# ADC.net
KiCad netlist of a schematic drawn in Altium Designer
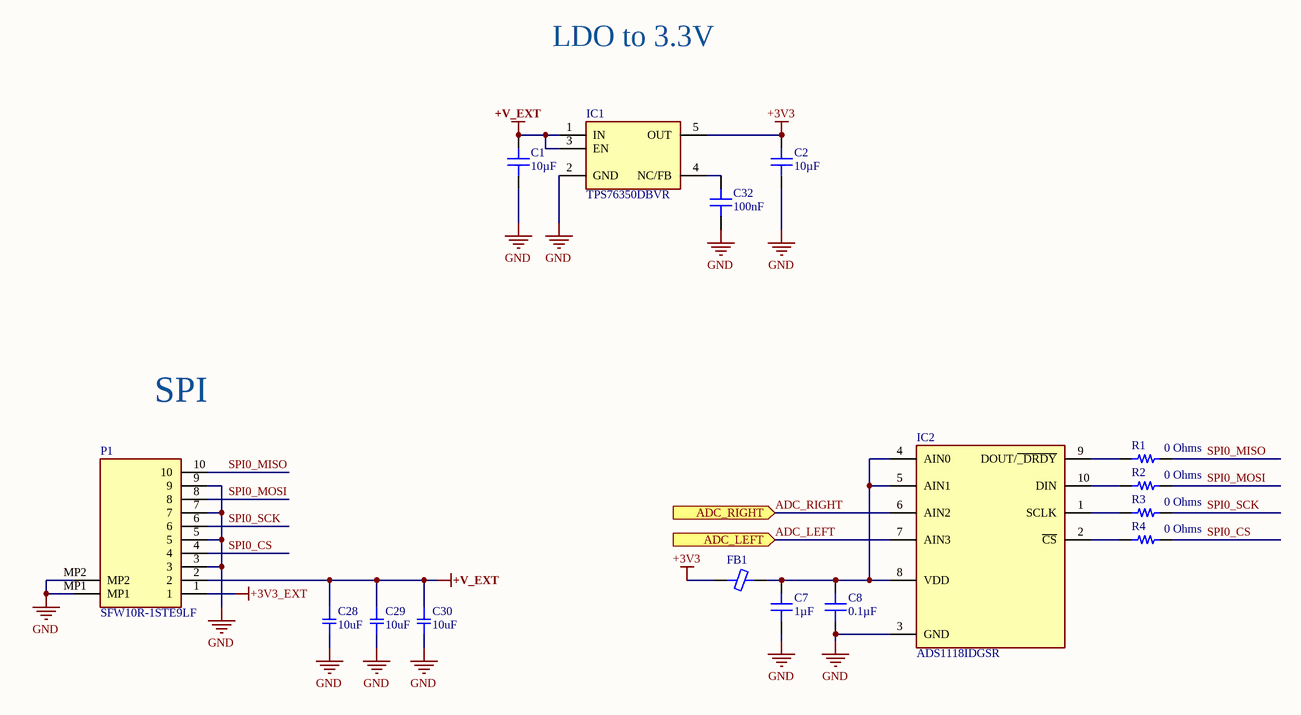
[diagram p0: ADC.SchDoc]

(export (version "E")
  (design (tool "Eeschema 10.0.6"))
  (components
    (comp (ref "C1")
      (value "10µF")
      (footprint "CAP 0603_1608")
      (description "CAP CER 0.1UF 10V X7R 0603")
      (fields (field (name "PART NUMBER") "100X14W104MV4T"))
      (libsource (lib "Celestial Altium Library - altium_library") (part "Capacitor"))
    )
    (comp (ref "C2")
      (value "10µF")
      (footprint "CAP 0603_1608")
      (description "CAP CER 0.1UF 10V X7R 0603")
      (fields (field (name "PART NUMBER") "100X14W104MV4T"))
      (libsource (lib "Celestial Altium Library - altium_library") (part "Capacitor"))
    )
    (comp (ref "C7")
      (value "1µF")
      (footprint "CAP 0603_1608")
      (description "CAP CER 0.1UF 10V X7R 0603")
      (fields (field (name "PART NUMBER") "100X14W104MV4T"))
      (libsource (lib "Celestial Altium Library - altium_library") (part "Capacitor"))
    )
    (comp (ref "C8")
      (value "0.1µF")
      (footprint "CAP 0603_1608")
      (description "CAP CER 0.1UF 10V X7R 0603")
      (fields (field (name "PART NUMBER") "100X14W104MV4T"))
      (libsource (lib "Celestial Altium Library - altium_library") (part "Capacitor"))
    )
    (comp (ref "C28")
      (value "10uF")
      (footprint "SMD-0805C")
      (description "CAP CER 10UF 10V X7R 0805")
      (fields
        (field (name "PART NUMBER") "GRJ21BR71A106KE01L")
        (field (name "DIGI-KEY PART NUMBER") "490-10919-1-ND")
      )
      (libsource (lib "cap_murata") (part "CAPACITOR"))
    )
    (comp (ref "C29")
      (value "10uF")
      (footprint "SMD-0805C")
      (description "CAP CER 10UF 10V X7R 0805")
      (fields
        (field (name "PART NUMBER") "GRJ21BR71A106KE01L")
        (field (name "DIGI-KEY PART NUMBER") "490-10919-1-ND")
      )
      (libsource (lib "cap_murata") (part "CAPACITOR"))
    )
    (comp (ref "C30")
      (value "10uF")
      (footprint "SMD-0805C")
      (description "CAP CER 10UF 10V X7R 0805")
      (fields
        (field (name "PART NUMBER") "GRJ21BR71A106KE01L")
        (field (name "DIGI-KEY PART NUMBER") "490-10919-1-ND")
      )
      (libsource (lib "cap_murata") (part "CAPACITOR"))
    )
    (comp (ref "C32")
      (value "100nF")
      (footprint "CAP 0603_1608")
      (description "CAP CER 0.1UF 10V X7R 0603")
      (fields (field (name "PART NUMBER") "100X14W104MV4T"))
      (libsource (lib "Celestial Altium Library - altium_library") (part "Capacitor"))
    )
    (comp (ref "FB1")
      (value "~")
      (footprint "FER 0603_1608")
      (description "FERRITE BEAD 0603 1LN")
      (fields (field (name "PART NUMBER") "2506031217H0"))
      (libsource (lib "Celestial Altium Library - altium_library") (part "Ferrite Chip"))
    )
    (comp (ref "IC1")
      (value "TPS76350DBVR")
      (footprint "SamacSys:SOT95P280X145-5N")
      (description "Integrated Circuit")
      (fields (field (name "MOUSER PART NUMBER") "595-TPS76350DBVR"))
      (libsource (lib "SamacSys") (part "TPS76350DBVR"))
    )
    (comp (ref "IC2")
      (value "ADS1118IDGSR")
      (footprint "SamacSys:SOP50P490X110-10N")
      (description "16-Bit")
      (fields (field (name "MOUSER PART NUMBER") "595-ADS1118IDGSR"))
      (libsource (lib "SamacSys") (part "ADS1118IDGSR"))
    )
    (comp (ref "P1")
      (value "SFW10R-1STE9LF")
      (footprint "SamacSys:SFW10R1STE9LF")
      (description "Connector")
      (fields (field (name "MOUSER PART NUMBER") "649-SFW10R-1STE9LF"))
      (libsource (lib "*") (part "SFW10R-1STE9LF"))
    )
    (comp (ref "R1")
      (value "0 Ohms")
      (footprint "PCB - RESISTOR - CHIP - STACKPOLE CSR0603:RES 0603_1608")
      (description "RES 100 OHM 0.1% 1/16W 0603")
      (fields (field (name "PART NUMBER") "RNCS0603BKE100R"))
      (libsource (lib "Celestial Altium Library - altium_library") (part "Resistor"))
    )
    (comp (ref "R2")
      (value "0 Ohms")
      (footprint "PCB - RESISTOR - CHIP - STACKPOLE CSR0603:RES 0603_1608")
      (description "RES 100 OHM 0.1% 1/16W 0603")
      (fields (field (name "PART NUMBER") "RNCS0603BKE100R"))
      (libsource (lib "Celestial Altium Library - altium_library") (part "Resistor"))
    )
    (comp (ref "R3")
      (value "0 Ohms")
      (footprint "PCB - RESISTOR - CHIP - STACKPOLE CSR0603:RES 0603_1608")
      (description "RES 100 OHM 0.1% 1/16W 0603")
      (fields (field (name "PART NUMBER") "RNCS0603BKE100R"))
      (libsource (lib "Celestial Altium Library - altium_library") (part "Resistor"))
    )
    (comp (ref "R4")
      (value "0 Ohms")
      (footprint "PCB - RESISTOR - CHIP - STACKPOLE CSR0603:RES 0603_1608")
      (description "RES 100 OHM 0.1% 1/16W 0603")
      (fields (field (name "PART NUMBER") "RNCS0603BKE100R"))
      (libsource (lib "Celestial Altium Library - altium_library") (part "Resistor"))
    )
  )
  (nets
    (net (code "1") (name "+3V3") (class "Default")
      (node (ref "C2") (pin "2") (pinfunction "2_2") (pintype "passive"))
      (node (ref "FB1") (pin "1") (pinfunction "1_1") (pintype "passive"))
      (node (ref "IC1") (pin "5") (pinfunction "OUT_5") (pintype "passive"))
    )
    (net (code "2") (name "+3V3_EXT") (class "Default")
      (node (ref "P1") (pin "1") (pinfunction "1_1") (pintype "passive"))
    )
    (net (code "3") (name "+V_EXT") (class "Default")
      (node (ref "C1") (pin "2") (pinfunction "2_2") (pintype "passive"))
      (node (ref "C28") (pin "1") (pinfunction "1_1") (pintype "passive"))
      (node (ref "C29") (pin "1") (pinfunction "1_1") (pintype "passive"))
      (node (ref "C30") (pin "1") (pinfunction "1_1") (pintype "passive"))
      (node (ref "IC1") (pin "1") (pinfunction "IN_1") (pintype "passive"))
      (node (ref "IC1") (pin "3") (pinfunction "EN_3") (pintype "passive"))
      (node (ref "P1") (pin "2") (pinfunction "2_2") (pintype "passive"))
    )
    (net (code "4") (name "/ADC_LEFT") (class "Default")
      (node (ref "IC2") (pin "7") (pinfunction "AIN3_7") (pintype "passive"))
    )
    (net (code "5") (name "/ADC_RIGHT") (class "Default")
      (node (ref "IC2") (pin "6") (pinfunction "AIN2_6") (pintype "passive"))
    )
    (net (code "6") (name "/SPI0_CS") (class "Default")
      (node (ref "P1") (pin "4") (pinfunction "4_4") (pintype "passive"))
      (node (ref "R4") (pin "1") (pinfunction "1_1") (pintype "passive"))
    )
    (net (code "7") (name "/SPI0_MISO") (class "Default")
      (node (ref "P1") (pin "10") (pinfunction "10_10") (pintype "passive"))
      (node (ref "R1") (pin "1") (pinfunction "1_1") (pintype "passive"))
    )
    (net (code "8") (name "/SPI0_MOSI") (class "Default")
      (node (ref "P1") (pin "8") (pinfunction "8_8") (pintype "passive"))
      (node (ref "R2") (pin "1") (pinfunction "1_1") (pintype "passive"))
    )
    (net (code "9") (name "/SPI0_SCK") (class "Default")
      (node (ref "P1") (pin "6") (pinfunction "6_6") (pintype "passive"))
      (node (ref "R3") (pin "1") (pinfunction "1_1") (pintype "passive"))
    )
    (net (code "10") (name "GND") (class "Default")
      (node (ref "C1") (pin "1") (pinfunction "1_1") (pintype "passive"))
      (node (ref "C2") (pin "1") (pinfunction "1_1") (pintype "passive"))
      (node (ref "C28") (pin "2") (pinfunction "2_2") (pintype "passive"))
      (node (ref "C29") (pin "2") (pinfunction "2_2") (pintype "passive"))
      (node (ref "C30") (pin "2") (pinfunction "2_2") (pintype "passive"))
      (node (ref "C32") (pin "1") (pinfunction "1_1") (pintype "passive"))
      (node (ref "C7") (pin "1") (pinfunction "1_1") (pintype "passive"))
      (node (ref "C8") (pin "1") (pinfunction "1_1") (pintype "passive"))
      (node (ref "IC1") (pin "2") (pinfunction "GND_2") (pintype "passive"))
      (node (ref "IC2") (pin "3") (pinfunction "GND_3") (pintype "passive"))
      (node (ref "P1") (pin "3") (pinfunction "3_3") (pintype "passive"))
      (node (ref "P1") (pin "5") (pinfunction "5_5") (pintype "passive"))
      (node (ref "P1") (pin "7") (pinfunction "7_7") (pintype "passive"))
      (node (ref "P1") (pin "9") (pinfunction "9_9") (pintype "passive"))
      (node (ref "P1") (pin "MP1") (pinfunction "MP1_MP1") (pintype "passive"))
      (node (ref "P1") (pin "MP2") (pinfunction "MP2_MP2") (pintype "passive"))
    )
    (net (code "11") (name "Net-(IC1-NC{slash}FB)") (class "Default")
      (node (ref "C32") (pin "2") (pinfunction "2_2") (pintype "passive"))
      (node (ref "IC1") (pin "4") (pinfunction "NC/FB_4") (pintype "passive"))
    )
    (net (code "12") (name "Net-(IC2-AIN0)") (class "Default")
      (node (ref "C7") (pin "2") (pinfunction "2_2") (pintype "passive"))
      (node (ref "C8") (pin "2") (pinfunction "2_2") (pintype "passive"))
      (node (ref "FB1") (pin "2") (pinfunction "2_2") (pintype "passive"))
      (node (ref "IC2") (pin "4") (pinfunction "AIN0_4") (pintype "passive"))
      (node (ref "IC2") (pin "5") (pinfunction "AIN1_5") (pintype "passive"))
      (node (ref "IC2") (pin "8") (pinfunction "VDD_8") (pintype "passive"))
    )
    (net (code "13") (name "Net-(IC2-DIN)") (class "Default")
      (node (ref "IC2") (pin "10") (pinfunction "DIN_10") (pintype "passive"))
      (node (ref "R2") (pin "2") (pinfunction "2_2") (pintype "passive"))
    )
    (net (code "14") (name "Net-(IC2-DOUT{slash}~{_DRDY})") (class "Default")
      (node (ref "IC2") (pin "9") (pinfunction "DOUT/~{_DRDY}_9") (pintype "passive"))
      (node (ref "R1") (pin "2") (pinfunction "2_2") (pintype "passive"))
    )
    (net (code "15") (name "Net-(IC2-SCLK)") (class "Default")
      (node (ref "IC2") (pin "1") (pinfunction "SCLK_1") (pintype "passive"))
      (node (ref "R3") (pin "2") (pinfunction "2_2") (pintype "passive"))
    )
    (net (code "16") (name "Net-(IC2-~{CS})") (class "Default")
      (node (ref "IC2") (pin "2") (pinfunction "~{CS}_2") (pintype "passive"))
      (node (ref "R4") (pin "2") (pinfunction "2_2") (pintype "passive"))
    )
  )
)
